# Dual_Motor_Driver.net
KiCad netlist of a schematic drawn in EAGLE
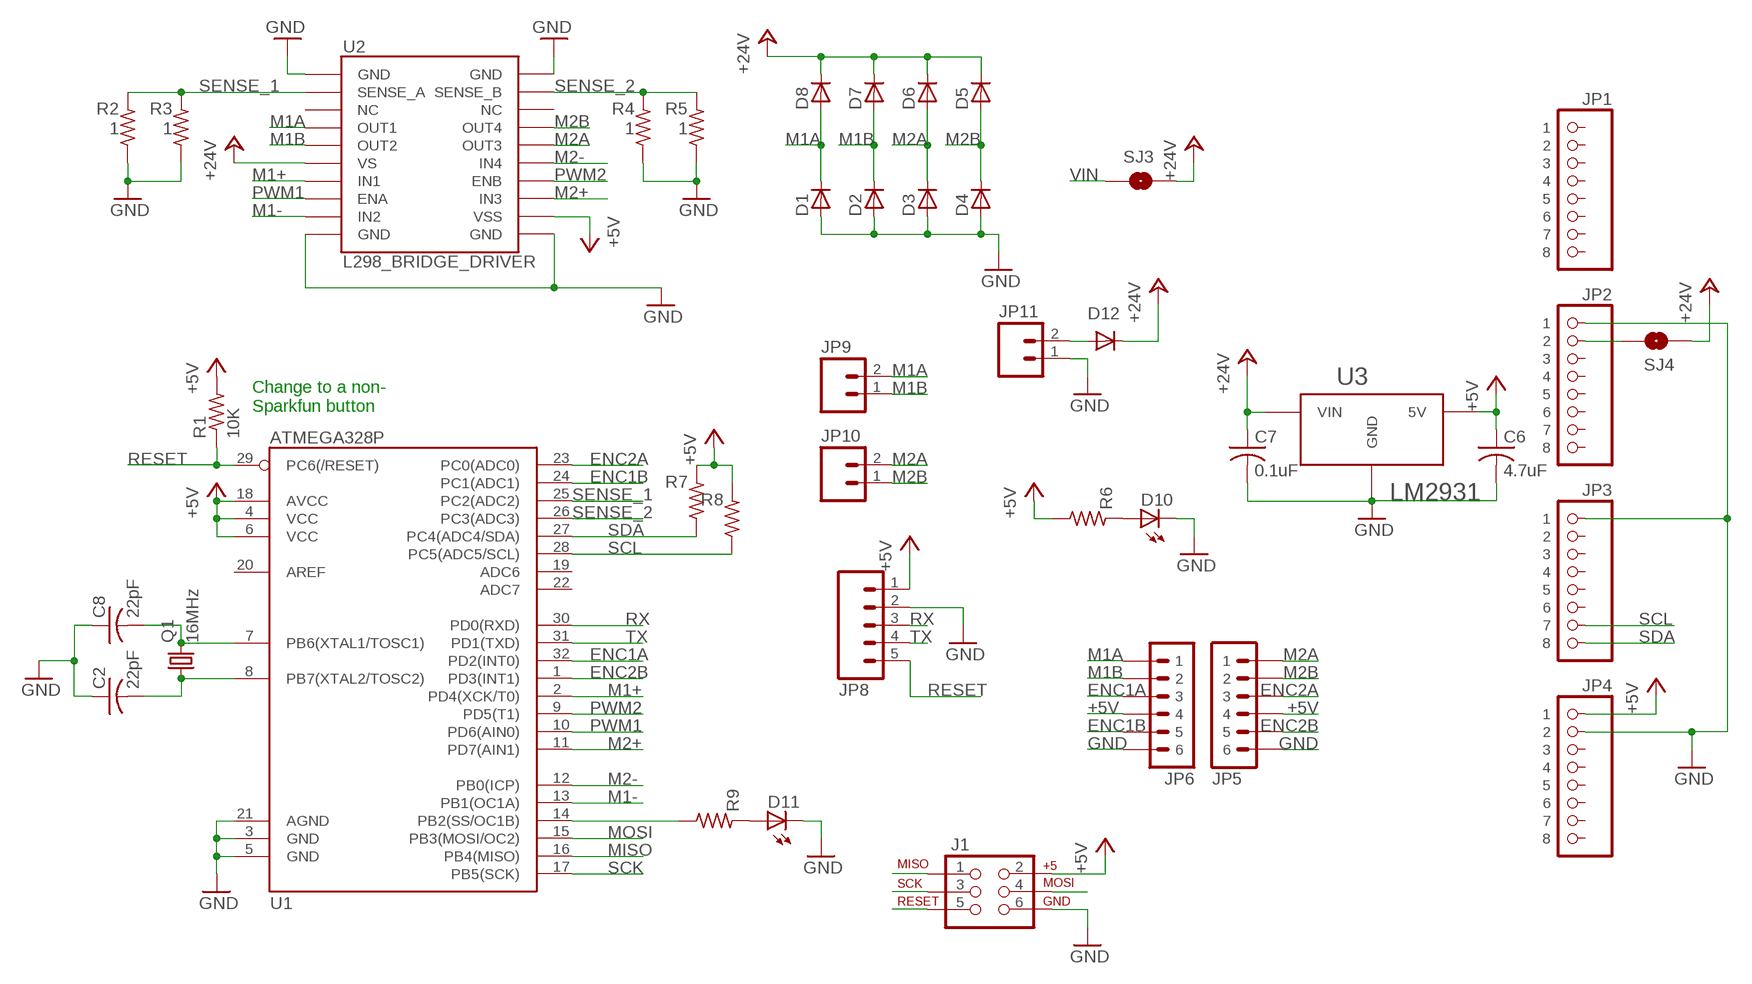
[diagram p0: schematic, sheet 1]

(export (version "E")
  (design (tool "Eeschema 10.0.6"))
  (components
    (comp (ref "C2")
      (value "22pF")
      (footprint "eagle-import:C0603")
      (libsource (lib "eagle-import") (part "C-USC0603"))
    )
    (comp (ref "C6")
      (value "4.7uF")
      (footprint "eagle-import:C0603")
      (libsource (lib "eagle-import") (part "C-USC0603"))
    )
    (comp (ref "C7")
      (value "0.1uF")
      (footprint "eagle-import:C0603")
      (libsource (lib "eagle-import") (part "C-USC0603"))
    )
    (comp (ref "C8")
      (value "22pF")
      (footprint "eagle-import:C0603")
      (libsource (lib "eagle-import") (part "C-USC0603"))
    )
    (comp (ref "D1")
      (value "D-SOD123")
      (footprint "eagle-import:SOD123")
      (fields (field (name "PART#") "CDBW140-G"))
      (libsource (lib "eagle-import") (part "D-SOD123"))
    )
    (comp (ref "D2")
      (value "D-SOD123")
      (footprint "eagle-import:SOD123")
      (fields (field (name "PART#") "CDBW140-G"))
      (libsource (lib "eagle-import") (part "D-SOD123"))
    )
    (comp (ref "D3")
      (value "D-SOD123")
      (footprint "eagle-import:SOD123")
      (fields (field (name "PART#") "CDBW140-G"))
      (libsource (lib "eagle-import") (part "D-SOD123"))
    )
    (comp (ref "D4")
      (value "D-SOD123")
      (footprint "eagle-import:SOD123")
      (fields (field (name "PART#") "CDBW140-G"))
      (libsource (lib "eagle-import") (part "D-SOD123"))
    )
    (comp (ref "D5")
      (value "D-SOD123")
      (footprint "eagle-import:SOD123")
      (fields (field (name "PART#") "CDBW140-G"))
      (libsource (lib "eagle-import") (part "D-SOD123"))
    )
    (comp (ref "D6")
      (value "D-SOD123")
      (footprint "eagle-import:SOD123")
      (fields (field (name "PART#") "CDBW140-G"))
      (libsource (lib "eagle-import") (part "D-SOD123"))
    )
    (comp (ref "D7")
      (value "D-SOD123")
      (footprint "eagle-import:SOD123")
      (fields (field (name "PART#") "CDBW140-G"))
      (libsource (lib "eagle-import") (part "D-SOD123"))
    )
    (comp (ref "D8")
      (value "D-SOD123")
      (footprint "eagle-import:SOD123")
      (fields (field (name "PART#") "CDBW140-G"))
      (libsource (lib "eagle-import") (part "D-SOD123"))
    )
    (comp (ref "D10")
      (value "LED-GREENLED-0805_NO_SILK")
      (footprint "eagle-import:LED-0805")
      (libsource (lib "eagle-import") (part "LED-GREENLED-0805_NO_SILK"))
    )
    (comp (ref "D11")
      (value "LED-GREENLED-0805_NO_SILK")
      (footprint "eagle-import:LED-0805")
      (libsource (lib "eagle-import") (part "LED-GREENLED-0805_NO_SILK"))
    )
    (comp (ref "D12")
      (value "DIODESMB")
      (footprint "eagle-import:SMB-DIODE")
      (libsource (lib "eagle-import") (part "DIODESMB"))
    )
    (comp (ref "J1")
      (value "AVR_SPI_PRG_62X3_LOCK")
      (footprint "eagle-import:2X3_LOCK")
      (libsource (lib "eagle-import") (part "AVR_SPI_PRG_62X3_LOCK"))
    )
    (comp (ref "JP1")
      (value "8-PIN_HEADER")
      (footprint "eagle-import:8-PIN_RECEPTACLE_LOCK_NO-SS")
      (libsource (lib "eagle-import") (part "8-PIN_HEADER"))
    )
    (comp (ref "JP2")
      (value "8-PIN_HEADER")
      (footprint "eagle-import:8-PIN_RECEPTACLE_LOCK_NO-SS")
      (libsource (lib "eagle-import") (part "8-PIN_HEADER"))
    )
    (comp (ref "JP3")
      (value "8-PIN_HEADER")
      (footprint "eagle-import:8-PIN_RECEPTACLE_LOCK_NO-SS")
      (libsource (lib "eagle-import") (part "8-PIN_HEADER"))
    )
    (comp (ref "JP4")
      (value "8-PIN_HEADER")
      (footprint "eagle-import:8-PIN_RECEPTACLE_LOCK_NO-SS")
      (libsource (lib "eagle-import") (part "8-PIN_HEADER"))
    )
    (comp (ref "JP5")
      (value "6PIN-SH_RIGHT_ANGLE")
      (footprint "eagle-import:6PIN-SH_SERIES_RA")
      (fields (field (name "PART#") "SM06B-SRSS-TB(LF)(SN)"))
      (libsource (lib "eagle-import") (part "6PIN-SH_RIGHT_ANGLE"))
    )
    (comp (ref "JP6")
      (value "6PIN-SH_RIGHT_ANGLE")
      (footprint "eagle-import:6PIN-SH_SERIES_RA")
      (fields (field (name "PART#") "SM06B-SRSS-TB(LF)(SN)"))
      (libsource (lib "eagle-import") (part "6PIN-SH_RIGHT_ANGLE"))
    )
    (comp (ref "JP8")
      (value "M05PTH")
      (footprint "eagle-import:1X05")
      (libsource (lib "eagle-import") (part "M05PTH"))
    )
    (comp (ref "JP9")
      (value "M02PTH")
      (footprint "eagle-import:1X02")
      (libsource (lib "eagle-import") (part "M02PTH"))
    )
    (comp (ref "JP10")
      (value "M02PTH")
      (footprint "eagle-import:1X02")
      (libsource (lib "eagle-import") (part "M02PTH"))
    )
    (comp (ref "JP11")
      (value "M02PTH")
      (footprint "eagle-import:1X02")
      (libsource (lib "eagle-import") (part "M02PTH"))
    )
    (comp (ref "Q1")
      (value "16MHz")
      (footprint "eagle-import:CTS406")
      (fields (field (name "PART#") "406C35D16M00000"))
      (libsource (lib "eagle-import") (part "CRYSTALCTS406"))
    )
    (comp (ref "R1")
      (value "10K")
      (footprint "eagle-import:R0603")
      (libsource (lib "eagle-import") (part "R-US_R0603"))
    )
    (comp (ref "R2")
      (value "1")
      (footprint "eagle-import:R0603")
      (libsource (lib "eagle-import") (part "R-US_R0603"))
    )
    (comp (ref "R3")
      (value "1")
      (footprint "eagle-import:R0603")
      (libsource (lib "eagle-import") (part "R-US_R0603"))
    )
    (comp (ref "R4")
      (value "1")
      (footprint "eagle-import:R0603")
      (libsource (lib "eagle-import") (part "R-US_R0603"))
    )
    (comp (ref "R5")
      (value "1")
      (footprint "eagle-import:R0603")
      (libsource (lib "eagle-import") (part "R-US_R0603"))
    )
    (comp (ref "R6")
      (value "R-US_R0603")
      (footprint "eagle-import:R0603")
      (libsource (lib "eagle-import") (part "R-US_R0603"))
    )
    (comp (ref "R7")
      (value "R-US_R0603")
      (footprint "eagle-import:R0603")
      (libsource (lib "eagle-import") (part "R-US_R0603"))
    )
    (comp (ref "R8")
      (value "R-US_R0603")
      (footprint "eagle-import:R0603")
      (libsource (lib "eagle-import") (part "R-US_R0603"))
    )
    (comp (ref "R9")
      (value "R-US_R0603")
      (footprint "eagle-import:R0603")
      (libsource (lib "eagle-import") (part "R-US_R0603"))
    )
    (comp (ref "SJ3")
      (value "SOLDERJUMPERNC")
      (footprint "eagle-import:SJ_2S")
      (libsource (lib "eagle-import") (part "SOLDERJUMPERNC"))
    )
    (comp (ref "SJ4")
      (value "SOLDERJUMPERTRACE")
      (footprint "eagle-import:SJ_2S-TRACE")
      (libsource (lib "eagle-import") (part "SOLDERJUMPERTRACE"))
    )
    (comp (ref "U1")
      (value "ATMEGA328P")
      (footprint "eagle-import:TQFP32-08")
      (libsource (lib "eagle-import") (part "ATMEGA328_SMT"))
    )
    (comp (ref "U2")
      (value "L298_BRIDGE_DRIVER")
      (footprint "eagle-import:POWERSO20")
      (libsource (lib "eagle-import") (part "L298_BRIDGE_DRIVER"))
    )
    (comp (ref "U3")
      (value "LM2931")
      (footprint "eagle-import:TO263")
      (libsource (lib "eagle-import") (part "LM2931"))
    )
  )
  (nets
    (net (code "1") (name "+5V") (class "Default")
      (node (ref "C6") (pin "1") (pinfunction "1_1") (pintype "passive"))
      (node (ref "J1") (pin "2") (pinfunction "2_2") (pintype "passive"))
      (node (ref "JP4") (pin "P$1") (pinfunction "1_P$1") (pintype "passive"))
      (node (ref "JP5") (pin "P$4") (pinfunction "4_P$4") (pintype "passive"))
      (node (ref "JP6") (pin "P$4") (pinfunction "4_P$4") (pintype "passive"))
      (node (ref "JP8") (pin "1") (pinfunction "1_1") (pintype "passive"))
      (node (ref "R1") (pin "2") (pinfunction "2_2") (pintype "passive"))
      (node (ref "R6") (pin "1") (pinfunction "1_1") (pintype "passive"))
      (node (ref "R7") (pin "2") (pinfunction "2_2") (pintype "passive"))
      (node (ref "R8") (pin "2") (pinfunction "2_2") (pintype "passive"))
      (node (ref "U1") (pin "18") (pinfunction "AVCC_18") (pintype "bidirectional"))
      (node (ref "U1") (pin "4") (pinfunction "VCC_4") (pintype "bidirectional"))
      (node (ref "U1") (pin "6") (pinfunction "VCC_6") (pintype "bidirectional"))
      (node (ref "U2") (pin "12") (pinfunction "VSS_12") (pintype "bidirectional"))
      (node (ref "U3") (pin "P$3") (pinfunction "5V_P$3") (pintype "bidirectional"))
    )
    (net (code "2") (name "+24V") (class "Default")
      (node (ref "C7") (pin "1") (pinfunction "1_1") (pintype "passive"))
      (node (ref "D12") (pin "C") (pinfunction "C_C") (pintype "passive"))
      (node (ref "D5") (pin "1") (pinfunction "C_1") (pintype "passive"))
      (node (ref "D6") (pin "1") (pinfunction "C_1") (pintype "passive"))
      (node (ref "D7") (pin "1") (pinfunction "C_1") (pintype "passive"))
      (node (ref "D8") (pin "1") (pinfunction "C_1") (pintype "passive"))
      (node (ref "SJ3") (pin "2") (pinfunction "2_2") (pintype "passive"))
      (node (ref "SJ4") (pin "1") (pinfunction "1_1") (pintype "passive"))
      (node (ref "U2") (pin "6") (pinfunction "VS_6") (pintype "bidirectional"))
      (node (ref "U3") (pin "P$2") (pinfunction "VIN_P$2") (pintype "bidirectional"))
    )
    (net (code "3") (name "/ENC1A") (class "Default")
      (node (ref "JP6") (pin "P$3") (pinfunction "3_P$3") (pintype "passive"))
      (node (ref "U1") (pin "32") (pinfunction "PD2(INT0)_32") (pintype "bidirectional"))
    )
    (net (code "4") (name "/ENC1B") (class "Default")
      (node (ref "JP6") (pin "P$5") (pinfunction "5_P$5") (pintype "passive"))
      (node (ref "U1") (pin "24") (pinfunction "PC1(ADC1)_24") (pintype "bidirectional"))
    )
    (net (code "5") (name "/ENC2A") (class "Default")
      (node (ref "JP5") (pin "P$3") (pinfunction "3_P$3") (pintype "passive"))
      (node (ref "U1") (pin "23") (pinfunction "PC0(ADC0)_23") (pintype "bidirectional"))
    )
    (net (code "6") (name "/ENC2B") (class "Default")
      (node (ref "JP5") (pin "P$5") (pinfunction "5_P$5") (pintype "passive"))
      (node (ref "U1") (pin "1") (pinfunction "PD3(INT1)_1") (pintype "bidirectional"))
    )
    (net (code "7") (name "/M1+") (class "Default")
      (node (ref "U1") (pin "2") (pinfunction "PD4(XCK/T0)_2") (pintype "bidirectional"))
      (node (ref "U2") (pin "7") (pinfunction "IN1_7") (pintype "bidirectional"))
    )
    (net (code "8") (name "/M1-") (class "Default")
      (node (ref "U1") (pin "13") (pinfunction "PB1(OC1A)_13") (pintype "bidirectional"))
      (node (ref "U2") (pin "9") (pinfunction "IN2_9") (pintype "bidirectional"))
    )
    (net (code "9") (name "/M1A") (class "Default")
      (node (ref "D1") (pin "1") (pinfunction "C_1") (pintype "passive"))
      (node (ref "D8") (pin "2") (pinfunction "A_2") (pintype "passive"))
      (node (ref "JP6") (pin "P$1") (pinfunction "1_P$1") (pintype "passive"))
      (node (ref "JP9") (pin "2") (pinfunction "2_2") (pintype "passive"))
      (node (ref "U2") (pin "4") (pinfunction "OUT1_4") (pintype "bidirectional"))
    )
    (net (code "10") (name "/M1B") (class "Default")
      (node (ref "D2") (pin "1") (pinfunction "C_1") (pintype "passive"))
      (node (ref "D7") (pin "2") (pinfunction "A_2") (pintype "passive"))
      (node (ref "JP6") (pin "P$2") (pinfunction "2_P$2") (pintype "passive"))
      (node (ref "JP9") (pin "1") (pinfunction "1_1") (pintype "passive"))
      (node (ref "U2") (pin "5") (pinfunction "OUT2_5") (pintype "bidirectional"))
    )
    (net (code "11") (name "/M2+") (class "Default")
      (node (ref "U1") (pin "11") (pinfunction "PD7(AIN1)_11") (pintype "bidirectional"))
      (node (ref "U2") (pin "13") (pinfunction "IN3_13") (pintype "bidirectional"))
    )
    (net (code "12") (name "/M2-") (class "Default")
      (node (ref "U1") (pin "12") (pinfunction "PB0(ICP)_12") (pintype "bidirectional"))
      (node (ref "U2") (pin "15") (pinfunction "IN4_15") (pintype "bidirectional"))
    )
    (net (code "13") (name "/M2A") (class "Default")
      (node (ref "D3") (pin "1") (pinfunction "C_1") (pintype "passive"))
      (node (ref "D6") (pin "2") (pinfunction "A_2") (pintype "passive"))
      (node (ref "JP10") (pin "2") (pinfunction "2_2") (pintype "passive"))
      (node (ref "JP5") (pin "P$1") (pinfunction "1_P$1") (pintype "passive"))
      (node (ref "U2") (pin "16") (pinfunction "OUT3_16") (pintype "bidirectional"))
    )
    (net (code "14") (name "/M2B") (class "Default")
      (node (ref "D4") (pin "1") (pinfunction "C_1") (pintype "passive"))
      (node (ref "D5") (pin "2") (pinfunction "A_2") (pintype "passive"))
      (node (ref "JP10") (pin "1") (pinfunction "1_1") (pintype "passive"))
      (node (ref "JP5") (pin "P$2") (pinfunction "2_P$2") (pintype "passive"))
      (node (ref "U2") (pin "17") (pinfunction "OUT4_17") (pintype "bidirectional"))
    )
    (net (code "15") (name "/MISO") (class "Default")
      (node (ref "J1") (pin "1") (pinfunction "1_1") (pintype "passive"))
      (node (ref "U1") (pin "16") (pinfunction "PB4(MISO)_16") (pintype "bidirectional"))
    )
    (net (code "16") (name "/MOSI") (class "Default")
      (node (ref "J1") (pin "4") (pinfunction "4_4") (pintype "passive"))
      (node (ref "U1") (pin "15") (pinfunction "PB3(MOSI/OC2)_15") (pintype "bidirectional"))
    )
    (net (code "17") (name "/PWM1") (class "Default")
      (node (ref "U1") (pin "10") (pinfunction "PD6(AIN0)_10") (pintype "bidirectional"))
      (node (ref "U2") (pin "8") (pinfunction "ENA_8") (pintype "bidirectional"))
    )
    (net (code "18") (name "/PWM2") (class "Default")
      (node (ref "U1") (pin "9") (pinfunction "PD5(T1)_9") (pintype "bidirectional"))
      (node (ref "U2") (pin "14") (pinfunction "ENB_14") (pintype "bidirectional"))
    )
    (net (code "19") (name "/RESET") (class "Default")
      (node (ref "J1") (pin "5") (pinfunction "5_5") (pintype "passive"))
      (node (ref "JP8") (pin "5") (pinfunction "5_5") (pintype "passive"))
      (node (ref "R1") (pin "1") (pinfunction "1_1") (pintype "passive"))
      (node (ref "U1") (pin "29") (pinfunction "PC6(/RESET)_29") (pintype "bidirectional"))
    )
    (net (code "20") (name "/RX") (class "Default")
      (node (ref "JP8") (pin "3") (pinfunction "3_3") (pintype "passive"))
      (node (ref "U1") (pin "30") (pinfunction "PD0(RXD)_30") (pintype "bidirectional"))
    )
    (net (code "21") (name "/SCK") (class "Default")
      (node (ref "J1") (pin "3") (pinfunction "3_3") (pintype "passive"))
      (node (ref "U1") (pin "17") (pinfunction "PB5(SCK)_17") (pintype "bidirectional"))
    )
    (net (code "22") (name "/SCL") (class "Default")
      (node (ref "JP3") (pin "P$7") (pinfunction "7_P$7") (pintype "passive"))
      (node (ref "R8") (pin "1") (pinfunction "1_1") (pintype "passive"))
      (node (ref "U1") (pin "28") (pinfunction "PC5(ADC5/SCL)_28") (pintype "bidirectional"))
    )
    (net (code "23") (name "/SDA") (class "Default")
      (node (ref "JP3") (pin "P$8") (pinfunction "8_P$8") (pintype "passive"))
      (node (ref "R7") (pin "1") (pinfunction "1_1") (pintype "passive"))
      (node (ref "U1") (pin "27") (pinfunction "PC4(ADC4/SDA)_27") (pintype "bidirectional"))
    )
    (net (code "24") (name "/SENSE_1") (class "Default")
      (node (ref "R2") (pin "2") (pinfunction "2_2") (pintype "passive"))
      (node (ref "R3") (pin "2") (pinfunction "2_2") (pintype "passive"))
      (node (ref "U1") (pin "25") (pinfunction "PC2(ADC2)_25") (pintype "bidirectional"))
      (node (ref "U2") (pin "2") (pinfunction "SENSE_A_2") (pintype "bidirectional"))
    )
    (net (code "25") (name "/SENSE_2") (class "Default")
      (node (ref "R4") (pin "2") (pinfunction "2_2") (pintype "passive"))
      (node (ref "R5") (pin "2") (pinfunction "2_2") (pintype "passive"))
      (node (ref "U1") (pin "26") (pinfunction "PC3(ADC3)_26") (pintype "bidirectional"))
      (node (ref "U2") (pin "19") (pinfunction "SENSE_B_19") (pintype "bidirectional"))
    )
    (net (code "26") (name "/TX") (class "Default")
      (node (ref "JP8") (pin "4") (pinfunction "4_4") (pintype "passive"))
      (node (ref "U1") (pin "31") (pinfunction "PD1(TXD)_31") (pintype "bidirectional"))
    )
    (net (code "27") (name "/VIN") (class "Default")
      (node (ref "D12") (pin "A") (pinfunction "A_A") (pintype "passive"))
      (node (ref "JP11") (pin "2") (pinfunction "2_2") (pintype "passive"))
      (node (ref "SJ3") (pin "1") (pinfunction "1_1") (pintype "passive"))
    )
    (net (code "28") (name "GND") (class "Default")
      (node (ref "C2") (pin "1") (pinfunction "1_1") (pintype "passive"))
      (node (ref "C6") (pin "2") (pinfunction "2_2") (pintype "passive"))
      (node (ref "C7") (pin "2") (pinfunction "2_2") (pintype "passive"))
      (node (ref "C8") (pin "1") (pinfunction "1_1") (pintype "passive"))
      (node (ref "D1") (pin "2") (pinfunction "A_2") (pintype "passive"))
      (node (ref "D10") (pin "2") (pinfunction "C_2") (pintype "passive"))
      (node (ref "D11") (pin "2") (pinfunction "C_2") (pintype "passive"))
      (node (ref "D2") (pin "2") (pinfunction "A_2") (pintype "passive"))
      (node (ref "D3") (pin "2") (pinfunction "A_2") (pintype "passive"))
      (node (ref "D4") (pin "2") (pinfunction "A_2") (pintype "passive"))
      (node (ref "J1") (pin "6") (pinfunction "6_6") (pintype "passive"))
      (node (ref "JP11") (pin "1") (pinfunction "1_1") (pintype "passive"))
      (node (ref "JP2") (pin "P$1") (pinfunction "1_P$1") (pintype "passive"))
      (node (ref "JP3") (pin "P$1") (pinfunction "1_P$1") (pintype "passive"))
      (node (ref "JP4") (pin "P$2") (pinfunction "2_P$2") (pintype "passive"))
      (node (ref "JP5") (pin "P$6") (pinfunction "6_P$6") (pintype "passive"))
      (node (ref "JP6") (pin "P$6") (pinfunction "6_P$6") (pintype "passive"))
      (node (ref "JP8") (pin "2") (pinfunction "2_2") (pintype "passive"))
      (node (ref "R2") (pin "1") (pinfunction "1_1") (pintype "passive"))
      (node (ref "R3") (pin "1") (pinfunction "1_1") (pintype "passive"))
      (node (ref "R4") (pin "1") (pinfunction "1_1") (pintype "passive"))
      (node (ref "R5") (pin "1") (pinfunction "1_1") (pintype "passive"))
      (node (ref "U1") (pin "21") (pinfunction "AGND_21") (pintype "bidirectional"))
      (node (ref "U1") (pin "3") (pinfunction "GND_3") (pintype "bidirectional"))
      (node (ref "U1") (pin "5") (pinfunction "GND_5") (pintype "bidirectional"))
      (node (ref "U2") (pin "1") (pinfunction "GND_1") (pintype "bidirectional"))
      (node (ref "U2") (pin "10") (pinfunction "GND_10") (pintype "bidirectional"))
      (node (ref "U2") (pin "11") (pinfunction "GND_11") (pintype "bidirectional"))
      (node (ref "U2") (pin "20") (pinfunction "GND_20") (pintype "bidirectional"))
      (node (ref "U3") (pin "P$1") (pinfunction "GND_P$1") (pintype "bidirectional"))
    )
    (net (code "29") (name "Net-(D10-A)") (class "Default")
      (node (ref "D10") (pin "1") (pinfunction "A_1") (pintype "passive"))
      (node (ref "R6") (pin "2") (pinfunction "2_2") (pintype "passive"))
    )
    (net (code "30") (name "Net-(D11-A)") (class "Default")
      (node (ref "D11") (pin "1") (pinfunction "A_1") (pintype "passive"))
      (node (ref "R9") (pin "2") (pinfunction "2_2") (pintype "passive"))
    )
    (net (code "31") (name "Net-(JP2-2)") (class "Default")
      (node (ref "JP2") (pin "P$2") (pinfunction "2_P$2") (pintype "passive"))
      (node (ref "SJ4") (pin "2") (pinfunction "2_2") (pintype "passive"))
    )
    (net (code "32") (name "Net-(Q1-2)") (class "Default")
      (node (ref "C8") (pin "2") (pinfunction "2_2") (pintype "passive"))
      (node (ref "Q1") (pin "3") (pinfunction "2_3") (pintype "passive"))
      (node (ref "U1") (pin "7") (pinfunction "PB6(XTAL1/TOSC1)_7") (pintype "bidirectional"))
    )
    (net (code "33") (name "Net-(U1-PB2(SS{slash}OC1B))") (class "Default")
      (node (ref "R9") (pin "1") (pinfunction "1_1") (pintype "passive"))
      (node (ref "U1") (pin "14") (pinfunction "PB2(SS/OC1B)_14") (pintype "bidirectional"))
    )
    (net (code "34") (name "Net-(U1-PB7(XTAL2{slash}TOSC2))") (class "Default")
      (node (ref "C2") (pin "2") (pinfunction "2_2") (pintype "passive"))
      (node (ref "Q1") (pin "1") (pinfunction "1_1") (pintype "passive"))
      (node (ref "U1") (pin "8") (pinfunction "PB7(XTAL2/TOSC2)_8") (pintype "bidirectional"))
    )
    (net (code "35") (name "unconnected-(JP1-1-PadP$1)") (class "Default")
      (node (ref "JP1") (pin "P$1") (pinfunction "1_P$1") (pintype "passive"))
    )
    (net (code "36") (name "unconnected-(JP1-2-PadP$2)") (class "Default")
      (node (ref "JP1") (pin "P$2") (pinfunction "2_P$2") (pintype "passive"))
    )
    (net (code "37") (name "unconnected-(JP1-3-PadP$3)") (class "Default")
      (node (ref "JP1") (pin "P$3") (pinfunction "3_P$3") (pintype "passive"))
    )
    (net (code "38") (name "unconnected-(JP1-4-PadP$4)") (class "Default")
      (node (ref "JP1") (pin "P$4") (pinfunction "4_P$4") (pintype "passive"))
    )
    (net (code "39") (name "unconnected-(JP1-5-PadP$5)") (class "Default")
      (node (ref "JP1") (pin "P$5") (pinfunction "5_P$5") (pintype "passive"))
    )
    (net (code "40") (name "unconnected-(JP1-6-PadP$6)") (class "Default")
      (node (ref "JP1") (pin "P$6") (pinfunction "6_P$6") (pintype "passive"))
    )
    (net (code "41") (name "unconnected-(JP1-7-PadP$7)") (class "Default")
      (node (ref "JP1") (pin "P$7") (pinfunction "7_P$7") (pintype "passive"))
    )
    (net (code "42") (name "unconnected-(JP1-8-PadP$8)") (class "Default")
      (node (ref "JP1") (pin "P$8") (pinfunction "8_P$8") (pintype "passive"))
    )
    (net (code "43") (name "unconnected-(JP2-3-PadP$3)") (class "Default")
      (node (ref "JP2") (pin "P$3") (pinfunction "3_P$3") (pintype "passive"))
    )
    (net (code "44") (name "unconnected-(JP2-4-PadP$4)") (class "Default")
      (node (ref "JP2") (pin "P$4") (pinfunction "4_P$4") (pintype "passive"))
    )
    (net (code "45") (name "unconnected-(JP2-5-PadP$5)") (class "Default")
      (node (ref "JP2") (pin "P$5") (pinfunction "5_P$5") (pintype "passive"))
    )
    (net (code "46") (name "unconnected-(JP2-6-PadP$6)") (class "Default")
      (node (ref "JP2") (pin "P$6") (pinfunction "6_P$6") (pintype "passive"))
    )
    (net (code "47") (name "unconnected-(JP2-7-PadP$7)") (class "Default")
      (node (ref "JP2") (pin "P$7") (pinfunction "7_P$7") (pintype "passive"))
    )
    (net (code "48") (name "unconnected-(JP2-8-PadP$8)") (class "Default")
      (node (ref "JP2") (pin "P$8") (pinfunction "8_P$8") (pintype "passive"))
    )
    (net (code "49") (name "unconnected-(JP3-2-PadP$2)") (class "Default")
      (node (ref "JP3") (pin "P$2") (pinfunction "2_P$2") (pintype "passive"))
    )
    (net (code "50") (name "unconnected-(JP3-3-PadP$3)") (class "Default")
      (node (ref "JP3") (pin "P$3") (pinfunction "3_P$3") (pintype "passive"))
    )
    (net (code "51") (name "unconnected-(JP3-4-PadP$4)") (class "Default")
      (node (ref "JP3") (pin "P$4") (pinfunction "4_P$4") (pintype "passive"))
    )
    (net (code "52") (name "unconnected-(JP3-5-PadP$5)") (class "Default")
      (node (ref "JP3") (pin "P$5") (pinfunction "5_P$5") (pintype "passive"))
    )
    (net (code "53") (name "unconnected-(JP3-6-PadP$6)") (class "Default")
      (node (ref "JP3") (pin "P$6") (pinfunction "6_P$6") (pintype "passive"))
    )
    (net (code "54") (name "unconnected-(JP4-3-PadP$3)") (class "Default")
      (node (ref "JP4") (pin "P$3") (pinfunction "3_P$3") (pintype "passive"))
    )
    (net (code "55") (name "unconnected-(JP4-4-PadP$4)") (class "Default")
      (node (ref "JP4") (pin "P$4") (pinfunction "4_P$4") (pintype "passive"))
    )
    (net (code "56") (name "unconnected-(JP4-5-PadP$5)") (class "Default")
      (node (ref "JP4") (pin "P$5") (pinfunction "5_P$5") (pintype "passive"))
    )
    (net (code "57") (name "unconnected-(JP4-6-PadP$6)") (class "Default")
      (node (ref "JP4") (pin "P$6") (pinfunction "6_P$6") (pintype "passive"))
    )
    (net (code "58") (name "unconnected-(JP4-7-PadP$7)") (class "Default")
      (node (ref "JP4") (pin "P$7") (pinfunction "7_P$7") (pintype "passive"))
    )
    (net (code "59") (name "unconnected-(JP4-8-PadP$8)") (class "Default")
      (node (ref "JP4") (pin "P$8") (pinfunction "8_P$8") (pintype "passive"))
    )
    (net (code "60") (name "unconnected-(U1-ADC6-Pad19)") (class "Default")
      (node (ref "U1") (pin "19") (pinfunction "ADC6_19") (pintype "bidirectional"))
    )
    (net (code "61") (name "unconnected-(U1-ADC7-Pad22)") (class "Default")
      (node (ref "U1") (pin "22") (pinfunction "ADC7_22") (pintype "bidirectional"))
    )
    (net (code "62") (name "unconnected-(U1-AREF-Pad20)") (class "Default")
      (node (ref "U1") (pin "20") (pinfunction "AREF_20") (pintype "bidirectional"))
    )
    (net (code "63") (name "unconnected-(U2-NC-Pad3)") (class "Default")
      (node (ref "U2") (pin "3") (pinfunction "NC_3") (pintype "bidirectional"))
    )
    (net (code "64") (name "unconnected-(U2-NC-Pad18)") (class "Default")
      (node (ref "U2") (pin "18") (pinfunction "NC_18") (pintype "bidirectional"))
    )
  )
)
